# SCH_Fisurometro_v2_2025-02-20.net
KiCad netlist of a schematic drawn in EasyEDA
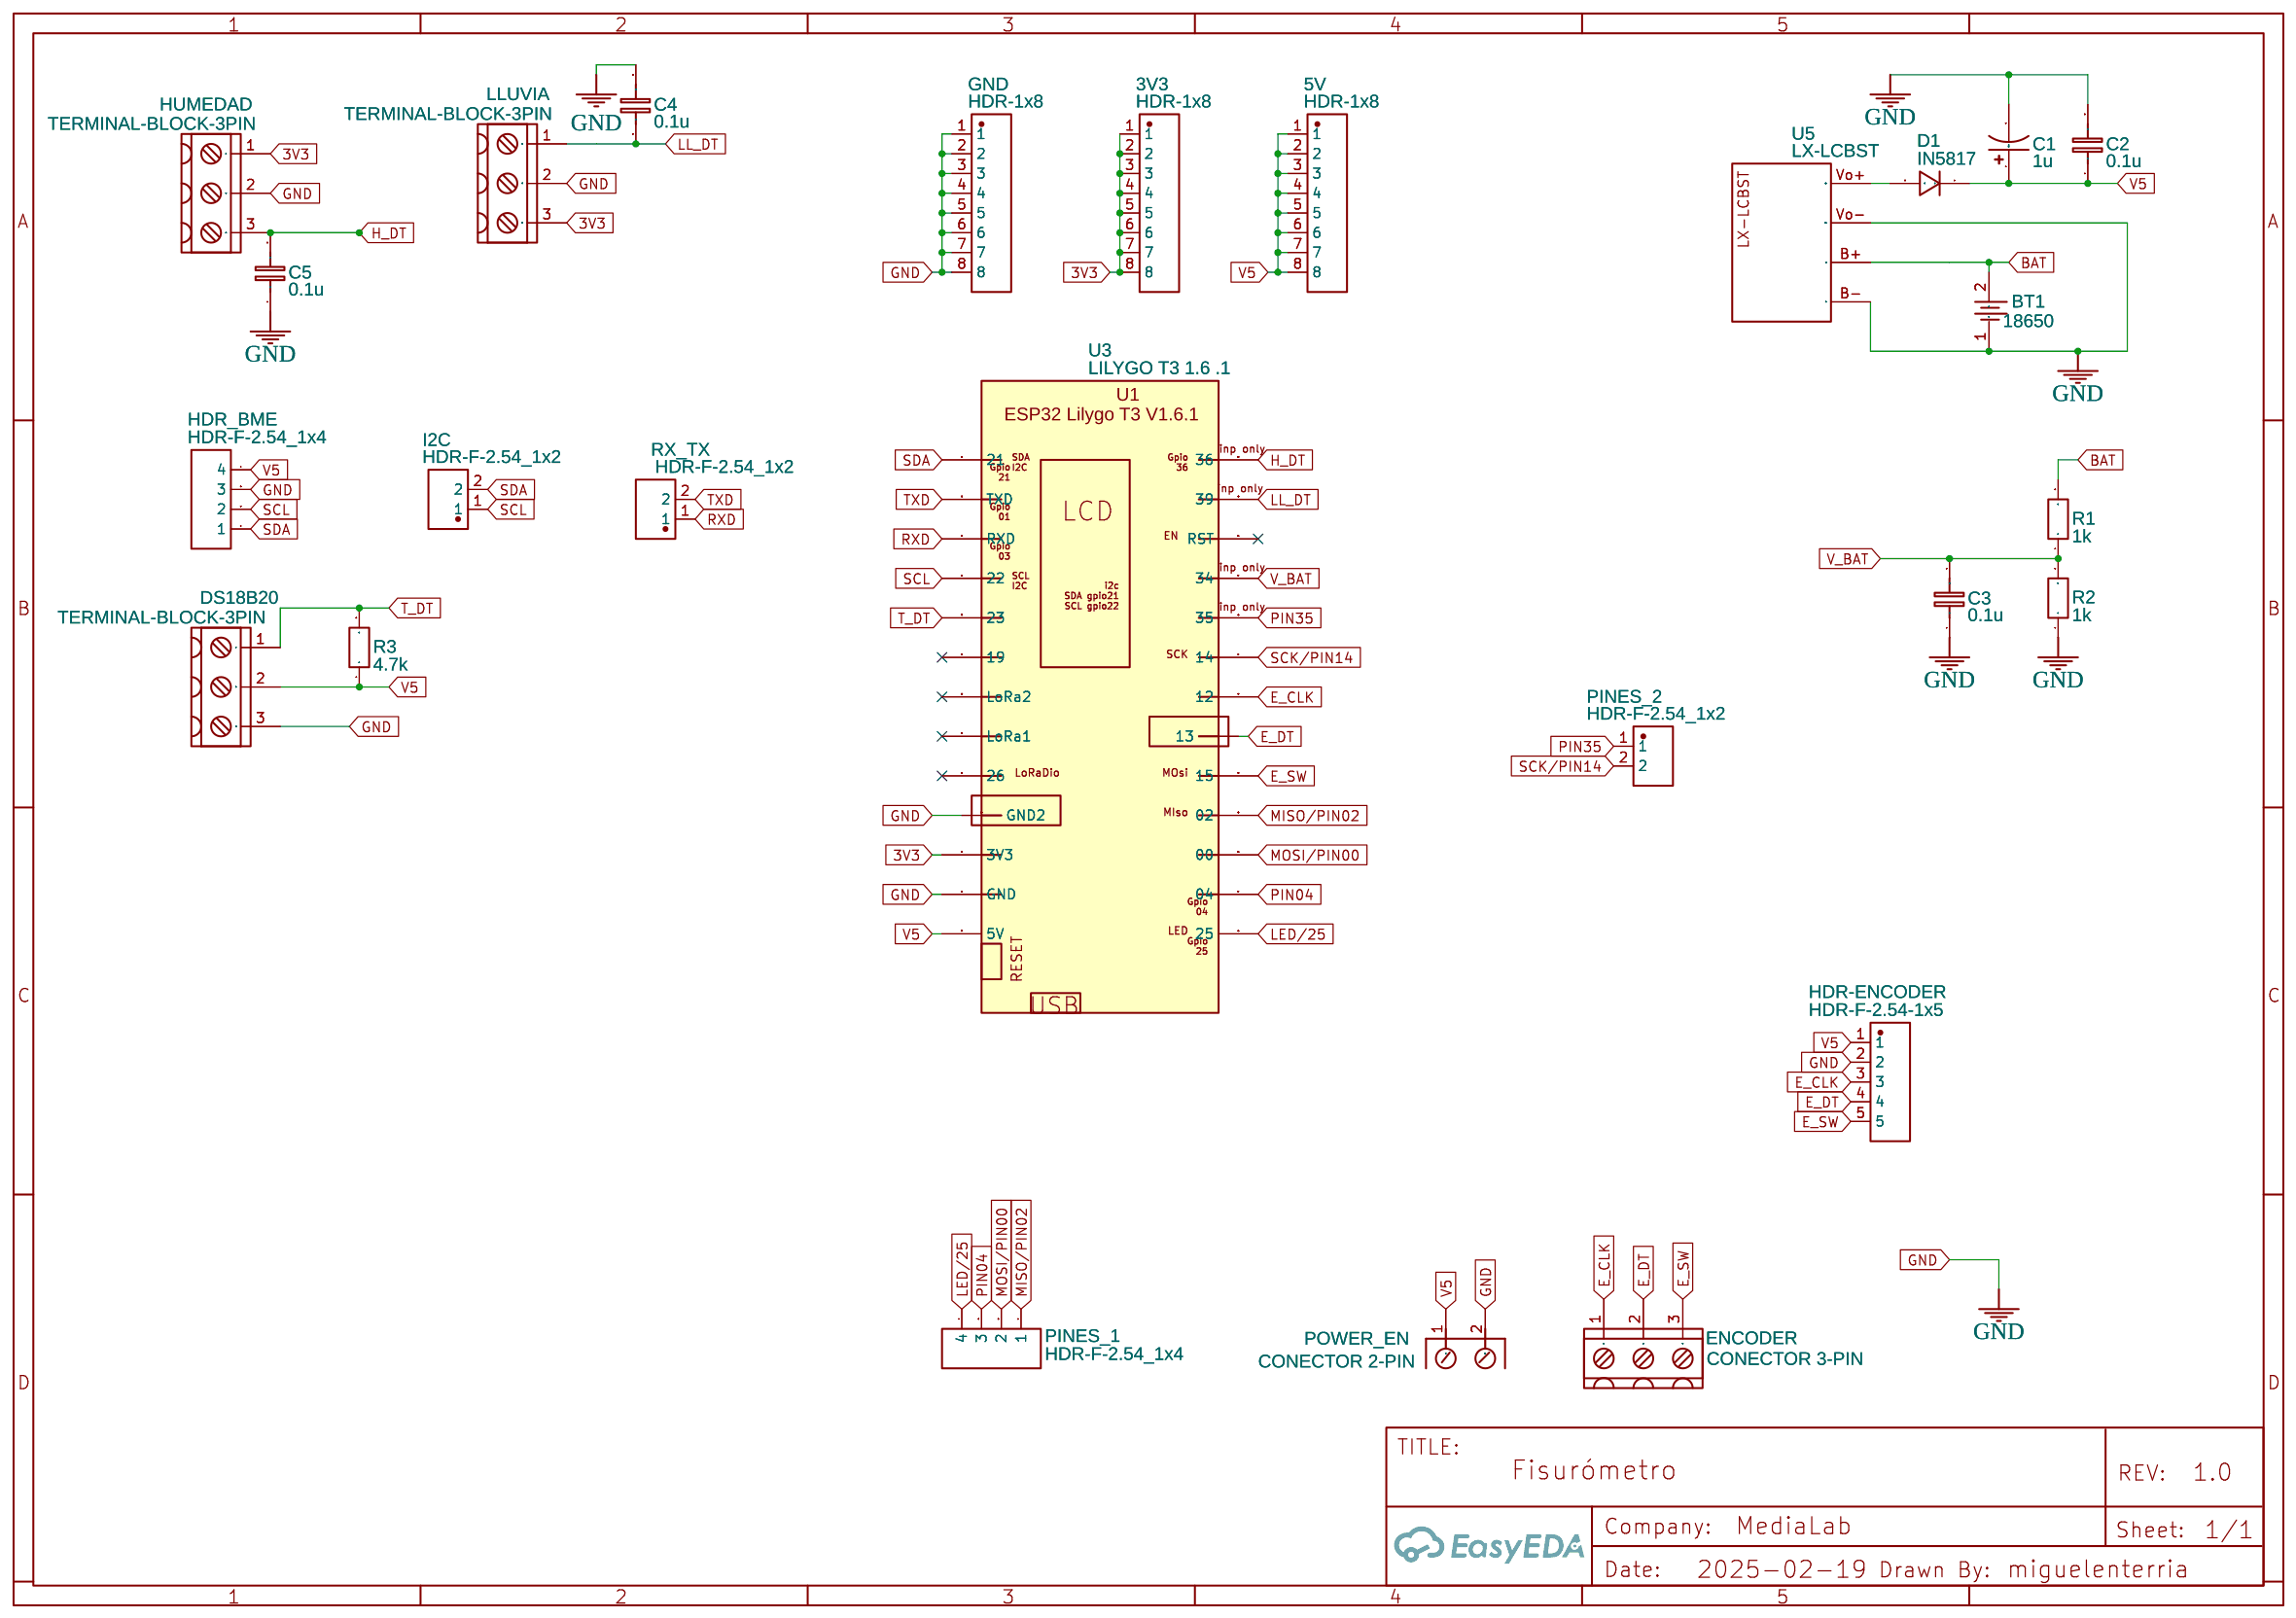
[diagram p0: schematic sheet]

(export (version "E")
  (design (tool "Eeschema 10.0.6"))
  (components
    (comp (ref "3V3") (value "HDR-1x8") (libsource (lib "") (part "HDR-1x8_1")))
    (comp (ref "5V") (value "HDR-1x8") (libsource (lib "") (part "HDR-1x8_2")))
    (comp (ref "BT1")
      (value "18650")
      (fields
        (field (name "Manufacturer Part") "BH-18650-A1AJ006")
        (field (name "Manufacturer") "MYOUNG(美阳)")
      )
      (libsource (lib "") (part "BH-18650-A1AJ006"))
    )
    (comp (ref "C1") (value "1u") (libsource (lib "") (part "CE_TH_D6.3×F2.5_US")))
    (comp (ref "C2") (value "0.1u") (libsource (lib "") (part "C_RAD-0.3_EU")))
    (comp (ref "C3") (value "0.1u") (libsource (lib "") (part "C_RAD-0.3_EU_1")))
    (comp (ref "C4") (value "0.1u") (libsource (lib "") (part "C_RAD-0.3_EU_2")))
    (comp (ref "C5") (value "0.1u") (libsource (lib "") (part "C_RAD-0.3_EU_2")))
    (comp (ref "D1")
      (value "IN5817")
      (fields (field (name "Manufacturer Part") "1N4007") (field (name "Manufacturer") "SEMTECH"))
      (libsource (lib "") (part "1N4007"))
    )
    (comp (ref "DS18B20")
      (value "TERMINAL-BLOCK-3PIN")
      (fields (field (name "Manufacturer Part") "Delhi") (field (name "Manufacturer") "Keltron"))
      (libsource (lib "") (part "TERMINAL-BLOCK-3PIN_3"))
    )
    (comp (ref "ENCODER")
      (value "CONECTOR 3-PIN")
      (fields (field (name "Manufacturer Part") "Delhi") (field (name "Manufacturer") "Keltron"))
      (libsource (lib "") (part "TERMINAL-BLOCK-3PIN"))
    )
    (comp (ref "GND") (value "HDR-1x8") (libsource (lib "") (part "HDR-1x8")))
    (comp (ref "HDR-ENCODER")
      (value "HDR-F-2.54-1x5")
      (fields (field (name "Manufacturer Part") "HDR-1X5"))
      (libsource (lib "") (part "HDR-1X5_C9900008152"))
    )
    (comp (ref "HDR_BME") (value "HDR-F-2.54_1x4") (libsource (lib "") (part "HDR-F-2.54_1x4_1")))
    (comp (ref "HUMEDAD")
      (value "TERMINAL-BLOCK-3PIN")
      (fields (field (name "Manufacturer Part") "Delhi") (field (name "Manufacturer") "Keltron"))
      (libsource (lib "") (part "TERMINAL-BLOCK-3PIN_2"))
    )
    (comp (ref "I2C")
      (value "HDR-F-2.54_1x2")
      (fields
        (field (name "Manufacturer Part") "HC-PZ254-11.5L-1x2PZ")
        (field (name "Manufacturer") "HC(虹成电子)")
      )
      (libsource (lib "") (part "HC-PZ254-11.5L-1X2PZ"))
    )
    (comp (ref "LLUVIA")
      (value "TERMINAL-BLOCK-3PIN")
      (fields (field (name "Manufacturer Part") "Delhi") (field (name "Manufacturer") "Keltron"))
      (libsource (lib "") (part "TERMINAL-BLOCK-3PIN_1"))
    )
    (comp (ref "PINES_1") (value "HDR-F-2.54_1x4") (libsource (lib "") (part "HDR-F-2.54_1x4")))
    (comp (ref "PINES_2")
      (value "HDR-F-2.54_1x2")
      (fields
        (field (name "Manufacturer Part") "HC-PZ254-11.5L-1x2PZ")
        (field (name "Manufacturer") "HC(虹成电子)")
      )
      (libsource (lib "") (part "HC-PZ254-11.5L-1X2PZ_2"))
    )
    (comp (ref "POWER_EN") (value "CONECTOR 2-PIN") (libsource (lib "") (part "2pin-5A_TerminalBlock")))
    (comp (ref "R1") (value "1k") (libsource (lib "") (part "R_AXIAL-0.6_EU")))
    (comp (ref "R2") (value "1k") (libsource (lib "") (part "R_AXIAL-0.6_EU")))
    (comp (ref "R3") (value "4.7k") (libsource (lib "") (part "R_AXIAL-0.6_EU")))
    (comp (ref "RX_TX")
      (value "HDR-F-2.54_1x2")
      (fields
        (field (name "Manufacturer Part") "HC-PZ254-11.5L-1x2PZ")
        (field (name "Manufacturer") "HC(虹成电子)")
      )
      (libsource (lib "") (part "HC-PZ254-11.5L-1X2PZ_1"))
    )
    (comp (ref "U3")
      (value "LILYGO T3 1.6 .1")
      (fields (field (name "Manufacturer Part") "LILYGO T3 1.6"))
      (libsource (lib "") (part "LILYGO T3 1.6 .1"))
    )
    (comp (ref "U5") (value "LX-LCBST") (libsource (lib "") (part "LX-LCBST")))
  )
  (nets
    (net (code "1") (name "3V3") (class "Default")
      (node (ref "3V3") (pin "1") (pinfunction "1_1") (pintype "unspecified"))
      (node (ref "3V3") (pin "2") (pinfunction "2_2") (pintype "unspecified"))
      (node (ref "3V3") (pin "3") (pinfunction "3_3") (pintype "unspecified"))
      (node (ref "3V3") (pin "4") (pinfunction "4_4") (pintype "unspecified"))
      (node (ref "3V3") (pin "5") (pinfunction "5_5") (pintype "unspecified"))
      (node (ref "3V3") (pin "6") (pinfunction "6_6") (pintype "unspecified"))
      (node (ref "3V3") (pin "7") (pinfunction "7_7") (pintype "unspecified"))
      (node (ref "3V3") (pin "8") (pinfunction "8_8") (pintype "unspecified"))
      (node (ref "HUMEDAD") (pin "1") (pinfunction "1_1") (pintype "unspecified"))
      (node (ref "LLUVIA") (pin "3") (pinfunction "3_3") (pintype "unspecified"))
      (node (ref "U3") (pin "3V3") (pinfunction "3V3_3V3") (pintype "passive"))
    )
    (net (code "2") (name "BAT") (class "Default")
      (node (ref "BT1") (pin "2") (pinfunction "2_2") (pintype "input"))
      (node (ref "R1") (pin "2") (pinfunction "2_2") (pintype "unspecified"))
      (node (ref "U5") (pin "B+") (pinfunction "B+_B+") (pintype "unspecified"))
    )
    (net (code "3") (name "E_CLK") (class "Default")
      (node (ref "ENCODER") (pin "1") (pinfunction "1_1") (pintype "unspecified"))
      (node (ref "HDR-ENCODER") (pin "3") (pinfunction "3_3") (pintype "unspecified"))
      (node (ref "U3") (pin "12") (pinfunction "12_12") (pintype "bidirectional"))
    )
    (net (code "4") (name "E_DT") (class "Default")
      (node (ref "ENCODER") (pin "2") (pinfunction "2_2") (pintype "unspecified"))
      (node (ref "HDR-ENCODER") (pin "4") (pinfunction "4_4") (pintype "unspecified"))
      (node (ref "U3") (pin "13") (pinfunction "13_13") (pintype "bidirectional"))
    )
    (net (code "5") (name "E_SW") (class "Default")
      (node (ref "ENCODER") (pin "3") (pinfunction "3_3") (pintype "unspecified"))
      (node (ref "HDR-ENCODER") (pin "5") (pinfunction "5_5") (pintype "unspecified"))
      (node (ref "U3") (pin "15") (pinfunction "15_15") (pintype "bidirectional"))
    )
    (net (code "6") (name "GND") (class "Default")
      (node (ref "BT1") (pin "1") (pinfunction "1_1") (pintype "input"))
      (node (ref "C1") (pin "2") (pinfunction "2_2") (pintype "unspecified"))
      (node (ref "C2") (pin "2") (pinfunction "2_2") (pintype "unspecified"))
      (node (ref "C3") (pin "1") (pinfunction "1_1") (pintype "unspecified"))
      (node (ref "C4") (pin "2") (pinfunction "2_2") (pintype "unspecified"))
      (node (ref "C5") (pin "1") (pinfunction "1_1") (pintype "unspecified"))
      (node (ref "DS18B20") (pin "3") (pinfunction "3_3") (pintype "unspecified"))
      (node (ref "GND") (pin "1") (pinfunction "1_1") (pintype "unspecified"))
      (node (ref "GND") (pin "2") (pinfunction "2_2") (pintype "unspecified"))
      (node (ref "GND") (pin "3") (pinfunction "3_3") (pintype "unspecified"))
      (node (ref "GND") (pin "4") (pinfunction "4_4") (pintype "unspecified"))
      (node (ref "GND") (pin "5") (pinfunction "5_5") (pintype "unspecified"))
      (node (ref "GND") (pin "6") (pinfunction "6_6") (pintype "unspecified"))
      (node (ref "GND") (pin "7") (pinfunction "7_7") (pintype "unspecified"))
      (node (ref "GND") (pin "8") (pinfunction "8_8") (pintype "unspecified"))
      (node (ref "HDR-ENCODER") (pin "2") (pinfunction "2_2") (pintype "unspecified"))
      (node (ref "HDR_BME") (pin "3") (pinfunction "3_3") (pintype "unspecified"))
      (node (ref "HUMEDAD") (pin "2") (pinfunction "2_2") (pintype "unspecified"))
      (node (ref "LLUVIA") (pin "2") (pinfunction "2_2") (pintype "unspecified"))
      (node (ref "POWER_EN") (pin "2") (pinfunction "2_2") (pintype "unspecified"))
      (node (ref "R2") (pin "1") (pinfunction "1_1") (pintype "unspecified"))
      (node (ref "U3") (pin "GND") (pinfunction "GND_GND") (pintype "passive"))
      (node (ref "U3") (pin "GND2") (pinfunction "GND2_GND2") (pintype "passive"))
      (node (ref "U5") (pin "B-") (pinfunction "B-_B-") (pintype "unspecified"))
      (node (ref "U5") (pin "Vo-") (pinfunction "Vout-_Vo-") (pintype "unspecified"))
    )
    (net (code "7") (name "H_DT") (class "Default")
      (node (ref "C5") (pin "2") (pinfunction "2_2") (pintype "unspecified"))
      (node (ref "HUMEDAD") (pin "3") (pinfunction "3_3") (pintype "unspecified"))
      (node (ref "U3") (pin "36") (pinfunction "36_36") (pintype "bidirectional"))
    )
    (net (code "8") (name "LED{slash}25") (class "Default")
      (node (ref "PINES_1") (pin "4") (pinfunction "4_4") (pintype "unspecified"))
      (node (ref "U3") (pin "25") (pinfunction "25_25") (pintype "bidirectional"))
    )
    (net (code "9") (name "LL_DT") (class "Default")
      (node (ref "C4") (pin "1") (pinfunction "1_1") (pintype "unspecified"))
      (node (ref "LLUVIA") (pin "1") (pinfunction "1_1") (pintype "unspecified"))
      (node (ref "U3") (pin "39") (pinfunction "39_39") (pintype "bidirectional"))
    )
    (net (code "10") (name "MISO{slash}PIN02") (class "Default")
      (node (ref "PINES_1") (pin "1") (pinfunction "1_1") (pintype "unspecified"))
      (node (ref "U3") (pin "02") (pinfunction "02_02") (pintype "bidirectional"))
    )
    (net (code "11") (name "MOSI{slash}PIN00") (class "Default")
      (node (ref "PINES_1") (pin "2") (pinfunction "2_2") (pintype "unspecified"))
      (node (ref "U3") (pin "00") (pinfunction "00_00") (pintype "bidirectional"))
    )
    (net (code "12") (name "Net-(U5-Vout+)") (class "Default")
      (node (ref "D1") (pin "2") (pinfunction "2_2") (pintype "unspecified"))
      (node (ref "U5") (pin "Vo+") (pinfunction "Vout+_Vo+") (pintype "unspecified"))
    )
    (net (code "13") (name "PIN04") (class "Default")
      (node (ref "PINES_1") (pin "3") (pinfunction "3_3") (pintype "unspecified"))
      (node (ref "U3") (pin "04") (pinfunction "04_04") (pintype "bidirectional"))
    )
    (net (code "14") (name "PIN35") (class "Default")
      (node (ref "PINES_2") (pin "1") (pinfunction "1_1") (pintype "unspecified"))
      (node (ref "U3") (pin "35") (pinfunction "35_35") (pintype "bidirectional"))
    )
    (net (code "15") (name "RXD") (class "Default")
      (node (ref "RX_TX") (pin "1") (pinfunction "1_1") (pintype "unspecified"))
      (node (ref "U3") (pin "RXD") (pinfunction "RXD_RXD") (pintype "unspecified"))
    )
    (net (code "16") (name "SCK{slash}PIN14") (class "Default")
      (node (ref "PINES_2") (pin "2") (pinfunction "2_2") (pintype "unspecified"))
      (node (ref "U3") (pin "14") (pinfunction "14_14") (pintype "bidirectional"))
    )
    (net (code "17") (name "SCL") (class "Default")
      (node (ref "HDR_BME") (pin "2") (pinfunction "2_2") (pintype "unspecified"))
      (node (ref "I2C") (pin "1") (pinfunction "1_1") (pintype "unspecified"))
      (node (ref "U3") (pin "22") (pinfunction "22_22") (pintype "bidirectional"))
    )
    (net (code "18") (name "SDA") (class "Default")
      (node (ref "HDR_BME") (pin "1") (pinfunction "1_1") (pintype "unspecified"))
      (node (ref "I2C") (pin "2") (pinfunction "2_2") (pintype "unspecified"))
      (node (ref "U3") (pin "21") (pinfunction "21_21") (pintype "bidirectional"))
    )
    (net (code "19") (name "TXD") (class "Default")
      (node (ref "RX_TX") (pin "2") (pinfunction "2_2") (pintype "unspecified"))
      (node (ref "U3") (pin "TXD") (pinfunction "TXD_TXD") (pintype "unspecified"))
    )
    (net (code "20") (name "T_DT") (class "Default")
      (node (ref "DS18B20") (pin "1") (pinfunction "1_1") (pintype "unspecified"))
      (node (ref "R3") (pin "2") (pinfunction "2_2") (pintype "unspecified"))
      (node (ref "U3") (pin "23") (pinfunction "23_23") (pintype "bidirectional"))
    )
    (net (code "21") (name "V5") (class "Default")
      (node (ref "5V") (pin "1") (pinfunction "1_1") (pintype "unspecified"))
      (node (ref "5V") (pin "2") (pinfunction "2_2") (pintype "unspecified"))
      (node (ref "5V") (pin "3") (pinfunction "3_3") (pintype "unspecified"))
      (node (ref "5V") (pin "4") (pinfunction "4_4") (pintype "unspecified"))
      (node (ref "5V") (pin "5") (pinfunction "5_5") (pintype "unspecified"))
      (node (ref "5V") (pin "6") (pinfunction "6_6") (pintype "unspecified"))
      (node (ref "5V") (pin "7") (pinfunction "7_7") (pintype "unspecified"))
      (node (ref "5V") (pin "8") (pinfunction "8_8") (pintype "unspecified"))
      (node (ref "C1") (pin "1") (pinfunction "1_1") (pintype "unspecified"))
      (node (ref "C2") (pin "1") (pinfunction "1_1") (pintype "unspecified"))
      (node (ref "D1") (pin "1") (pinfunction "1_1") (pintype "unspecified"))
      (node (ref "DS18B20") (pin "2") (pinfunction "2_2") (pintype "unspecified"))
      (node (ref "HDR-ENCODER") (pin "1") (pinfunction "1_1") (pintype "unspecified"))
      (node (ref "HDR_BME") (pin "4") (pinfunction "4_4") (pintype "unspecified"))
      (node (ref "POWER_EN") (pin "1") (pinfunction "1_1") (pintype "unspecified"))
      (node (ref "R3") (pin "1") (pinfunction "1_1") (pintype "unspecified"))
      (node (ref "U3") (pin "5V") (pinfunction "5V_5V") (pintype "passive"))
    )
    (net (code "22") (name "V_BAT") (class "Default")
      (node (ref "C3") (pin "2") (pinfunction "2_2") (pintype "unspecified"))
      (node (ref "R1") (pin "1") (pinfunction "1_1") (pintype "unspecified"))
      (node (ref "R2") (pin "2") (pinfunction "2_2") (pintype "unspecified"))
      (node (ref "U3") (pin "34") (pinfunction "34_34") (pintype "bidirectional"))
    )
    (net (code "23") (name "unconnected-(U3-LoRa1-PadLORA1)") (class "Default")
      (node (ref "U3") (pin "LORA1") (pinfunction "LoRa1_LORA1") (pintype "bidirectional+no_connect"))
    )
    (net (code "24") (name "unconnected-(U3-LoRa2-PadLORA2)") (class "Default")
      (node (ref "U3") (pin "LORA2") (pinfunction "LoRa2_LORA2") (pintype "bidirectional+no_connect"))
    )
    (net (code "25") (name "unconnected-(U3-Pad19)") (class "Default")
      (node (ref "U3") (pin "19") (pinfunction "19_19") (pintype "bidirectional+no_connect"))
    )
    (net (code "26") (name "unconnected-(U3-Pad26)") (class "Default")
      (node (ref "U3") (pin "26") (pinfunction "26_26") (pintype "bidirectional+no_connect"))
    )
    (net (code "27") (name "unconnected-(U3-PadRST)") (class "Default")
      (node (ref "U3") (pin "RST") (pinfunction "RST_RST") (pintype "bidirectional+no_connect"))
    )
  )
)
